# usb_host_slave.net
KiCad netlist of a schematic drawn in Altium Designer
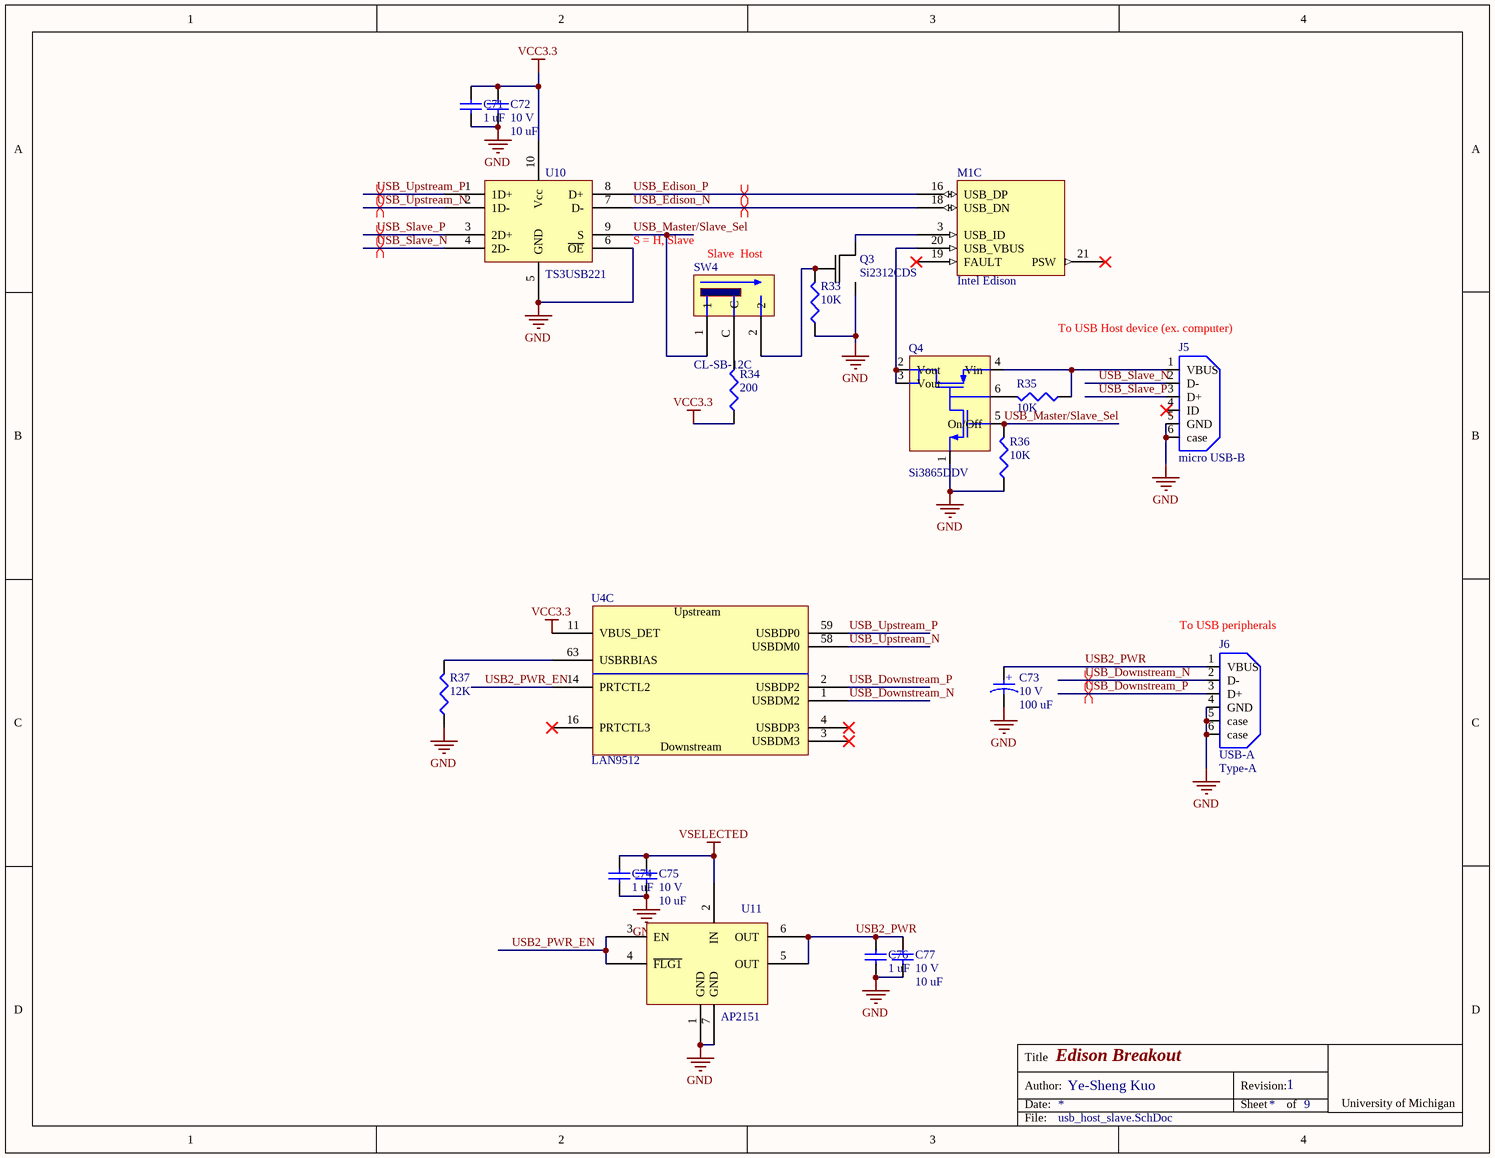
[diagram p0: usb_host_slave.SchDoc]

(export (version "E")
  (design (tool "Eeschema 10.0.6"))
  (components
    (comp (ref "C71")
      (value "1 uF")
      (footprint "0402")
      (description "Ceramic capacitor, 1 uF, 16V, 0402 package")
      (fields (field (name "TOLERANCE") "10%") (field (name "Comment") "Ceramic capacitor"))
      (libsource (lib "rlc") (part "C_1u_16V_0402_ceramic"))
    )
    (comp (ref "C72")
      (value "10 uF")
      (footprint "0603")
      (description "Ceramic capacitor, 10 uF, 10 V, 0603 package")
      (fields
        (field (name "TOLERANCE") "20%")
        (field (name "VOLTAGE RATED") "10 V")
        (field (name "Comment") "Ceramic capacitor")
      )
      (libsource (lib "rlc") (part "C_10u_10V_0603_ceramic"))
    )
    (comp (ref "C73")
      (value "100 uF")
      (footprint "1206 - POLAR MARKING")
      (description "Tantalum capacitor, 100 uF, 10 V, 1206 package")
      (fields
        (field (name "TOLERANCE") "20%")
        (field (name "VOLTAGE RATED") "10 V")
        (field (name "Comment") "Tantalum capacitor")
      )
      (libsource (lib "rlc") (part "C_100u_10V_1206_tantalum"))
    )
    (comp (ref "C74")
      (value "1 uF")
      (footprint "0402")
      (description "Ceramic capacitor, 1 uF, 16V, 0402 package")
      (fields (field (name "TOLERANCE") "10%") (field (name "Comment") "Ceramic capacitor"))
      (libsource (lib "rlc") (part "C_1u_16V_0402_ceramic"))
    )
    (comp (ref "C75")
      (value "10 uF")
      (footprint "0603")
      (description "Ceramic capacitor, 10 uF, 10 V, 0603 package")
      (fields
        (field (name "TOLERANCE") "20%")
        (field (name "VOLTAGE RATED") "10 V")
        (field (name "Comment") "Ceramic capacitor")
      )
      (libsource (lib "rlc") (part "C_10u_10V_0603_ceramic"))
    )
    (comp (ref "C76")
      (value "1 uF")
      (footprint "0402")
      (description "Ceramic capacitor, 1 uF, 16V, 0402 package")
      (fields (field (name "TOLERANCE") "10%") (field (name "Comment") "Ceramic capacitor"))
      (libsource (lib "rlc") (part "C_1u_16V_0402_ceramic"))
    )
    (comp (ref "C77")
      (value "10 uF")
      (footprint "0603")
      (description "Ceramic capacitor, 10 uF, 10 V, 0603 package")
      (fields
        (field (name "TOLERANCE") "20%")
        (field (name "VOLTAGE RATED") "10 V")
        (field (name "Comment") "Ceramic capacitor")
      )
      (libsource (lib "rlc") (part "C_10u_10V_0603_ceramic"))
    )
    (comp (ref "J5")
      (value "micro USB-B")
      (footprint "Micro USB-B")
      (description "CONN USB MICRO B RECPT SMT R/A")
      (libsource (lib "connectors") (part "Micro USB"))
    )
    (comp (ref "J6")
      (value "USB-A")
      (footprint "292303-2")
      (description "USB 2.0 Type A")
      (fields (field (name "TYPE") "Type-A"))
      (libsource (lib "connectors") (part "A105221-ND"))
    )
    (comp (ref "M1")
      (value "Intel Edison")
      (footprint "Intel Edison mating")
      (libsource (lib "edison") (part "Intel Edison"))
    )
    (comp (ref "Q3")
      (value "Si2312CDS")
      (footprint "SOT23-3")
      (description "N-Channel 20 V (D-S) MOSFET")
      (libsource (lib "transistors") (part "Si2312CDS"))
    )
    (comp (ref "Q4")
      (value "Si3865DDV")
      (footprint "TSOT-23")
      (description "Load Switch")
      (libsource (lib "power_switch") (part "Si3865DDV"))
    )
    (comp (ref "R33")
      (value "10K")
      (footprint "0402")
      (description "Chip resistor, 10K, 0402 package")
      (fields (field (name "TOLERANCE") "1%") (field (name "POWER") "1/16 W"))
      (libsource (lib "rlc") (part "R_10K_0402"))
    )
    (comp (ref "R34")
      (value "200")
      (footprint "0402")
      (description "Chip resistor, 200, 0402 package")
      (fields (field (name "TOLERANCE") "1%") (field (name "POWER") "1/16 W"))
      (libsource (lib "rlc") (part "R_200_0402"))
    )
    (comp (ref "R35")
      (value "10K")
      (footprint "0402")
      (description "Chip resistor, 10K, 0402 package")
      (fields (field (name "TOLERANCE") "1%") (field (name "POWER") "1/16 W"))
      (libsource (lib "rlc") (part "R_10K_0402"))
    )
    (comp (ref "R36")
      (value "10K")
      (footprint "0402")
      (description "Chip resistor, 10K, 0402 package")
      (fields (field (name "TOLERANCE") "1%") (field (name "POWER") "1/16 W"))
      (libsource (lib "rlc") (part "R_10K_0402"))
    )
    (comp (ref "R37")
      (value "12K")
      (footprint "0402")
      (description "Chip resistor, 12K, 0402 package")
      (fields (field (name "TOLERANCE") "1%") (field (name "POWER") "1/16 W"))
      (libsource (lib "rlc") (part "R_12K_0402"))
    )
    (comp (ref "SW4")
      (value "CL-SB-12C")
      (footprint "CL-SB-12C")
      (description "SPST Slide switch")
      (libsource (lib "switches") (part "CL-SB-12C"))
    )
    (comp (ref "U4")
      (value "LAN9512")
      (footprint "QFN-64")
      (description "USB 2.0 Hub and 10/100  Ethernet Controller")
      (libsource (lib "ethernet") (part "LAN9512"))
    )
    (comp (ref "U10")
      (value "TS3USB221")
      (footprint "PUQFN-10")
      (description "High-Speed USB 2.0 (480-Mbps) 1:2 Multiplexer – Demultiplexer  Switch With Single Enable")
      (libsource (lib "multiplexer") (part "TS3USB221"))
    )
    (comp (ref "U11")
      (value "AP2151")
      (footprint "U-DFN2018-6")
      (description "0.5A SINGLE CHANNEL CURRENT-LIMITED  POWER SWITCH WITH OUTPUT DISCHARGE")
      (libsource (lib "power_switch") (part "AP2151"))
    )
  )
  (nets
    (net (code "1") (name "/USB2_PWR") (class "Default")
      (node (ref "C73") (pin "1") (pintype "passive"))
      (node (ref "C76") (pin "1") (pintype "passive"))
      (node (ref "C77") (pin "1") (pintype "passive"))
      (node (ref "J6") (pin "1") (pinfunction "VBUS_1") (pintype "power_in"))
      (node (ref "U11") (pin "5") (pinfunction "OUT_5") (pintype "passive"))
      (node (ref "U11") (pin "6") (pinfunction "OUT_6") (pintype "passive"))
    )
    (net (code "2") (name "/USB2_PWR_EN") (class "Default")
      (node (ref "U11") (pin "3") (pinfunction "EN_3") (pintype "passive"))
      (node (ref "U11") (pin "4") (pinfunction "~{FLG1}_4") (pintype "passive"))
      (node (ref "U4") (pin "14") (pinfunction "PRTCTL2_14") (pintype "passive"))
    )
    (net (code "3") (name "/USB_Downstream_N") (class "Default")
      (node (ref "J6") (pin "2") (pinfunction "D-_2") (pintype "power_in"))
      (node (ref "U4") (pin "1") (pinfunction "USBDM2_1") (pintype "passive"))
    )
    (net (code "4") (name "/USB_Downstream_P") (class "Default")
      (node (ref "J6") (pin "3") (pinfunction "D+_3") (pintype "power_in"))
      (node (ref "U4") (pin "2") (pinfunction "USBDP2_2") (pintype "passive"))
    )
    (net (code "5") (name "/USB_Edison_N") (class "Default")
      (node (ref "M1") (pin "18") (pinfunction "USB_DN_18") (pintype "bidirectional"))
      (node (ref "U10") (pin "7") (pinfunction "D-_7") (pintype "passive"))
    )
    (net (code "6") (name "/USB_Edison_P") (class "Default")
      (node (ref "M1") (pin "16") (pinfunction "USB_DP_16") (pintype "bidirectional"))
      (node (ref "U10") (pin "8") (pinfunction "D+_8") (pintype "passive"))
    )
    (net (code "7") (name "/USB_Master{slash}Slave_Sel") (class "Default")
      (node (ref "Q4") (pin "5") (pinfunction "On/Off_5") (pintype "passive"))
      (node (ref "R36") (pin "1") (pintype "passive"))
      (node (ref "SW4") (pin "1") (pinfunction "1_1") (pintype "passive"))
      (node (ref "U10") (pin "9") (pinfunction "S_9") (pintype "passive"))
    )
    (net (code "8") (name "/USB_Slave_N") (class "Default")
      (node (ref "J5") (pin "2") (pinfunction "D-_2") (pintype "power_in"))
      (node (ref "U10") (pin "4") (pinfunction "2D-_4") (pintype "passive"))
    )
    (net (code "9") (name "/USB_Slave_P") (class "Default")
      (node (ref "J5") (pin "3") (pinfunction "D+_3") (pintype "power_in"))
      (node (ref "U10") (pin "3") (pinfunction "2D+_3") (pintype "passive"))
    )
    (net (code "10") (name "/USB_Upstream_N") (class "Default")
      (node (ref "U10") (pin "2") (pinfunction "1D-_2") (pintype "passive"))
      (node (ref "U4") (pin "58") (pinfunction "USBDM0_58") (pintype "passive"))
    )
    (net (code "11") (name "/USB_Upstream_P") (class "Default")
      (node (ref "U10") (pin "1") (pinfunction "1D+_1") (pintype "passive"))
      (node (ref "U4") (pin "59") (pinfunction "USBDP0_59") (pintype "passive"))
    )
    (net (code "12") (name "GND") (class "Default")
      (node (ref "C71") (pin "2") (pintype "passive"))
      (node (ref "C72") (pin "2") (pintype "passive"))
      (node (ref "C73") (pin "2") (pintype "passive"))
      (node (ref "C74") (pin "2") (pintype "passive"))
      (node (ref "C75") (pin "2") (pintype "passive"))
      (node (ref "C76") (pin "2") (pintype "passive"))
      (node (ref "C77") (pin "2") (pintype "passive"))
      (node (ref "J5") (pin "5") (pinfunction "GND_5") (pintype "power_in"))
      (node (ref "J5") (pin "6") (pinfunction "case_6") (pintype "power_in"))
      (node (ref "J6") (pin "4") (pinfunction "GND_4") (pintype "power_in"))
      (node (ref "J6") (pin "5") (pinfunction "case_5") (pintype "power_in"))
      (node (ref "J6") (pin "6") (pinfunction "case_6") (pintype "power_in"))
      (node (ref "Q3") (pin "2") (pinfunction "S_2") (pintype "passive"))
      (node (ref "Q4") (pin "1") (pintype "passive"))
      (node (ref "R33") (pin "2") (pintype "passive"))
      (node (ref "R36") (pin "2") (pintype "passive"))
      (node (ref "R37") (pin "2") (pintype "passive"))
      (node (ref "U10") (pin "5") (pinfunction "GND_5") (pintype "passive"))
      (node (ref "U10") (pin "6") (pinfunction "~{OE}_6") (pintype "passive"))
      (node (ref "U11") (pin "1") (pinfunction "GND_1") (pintype "passive"))
      (node (ref "U11") (pin "7") (pinfunction "GND_7") (pintype "passive"))
    )
    (net (code "13") (name "Net-(J5-VBUS)") (class "Default")
      (node (ref "J5") (pin "1") (pinfunction "VBUS_1") (pintype "power_in"))
      (node (ref "Q4") (pin "4") (pinfunction "Vin_4") (pintype "passive"))
      (node (ref "R35") (pin "2") (pintype "passive"))
    )
    (net (code "14") (name "Net-(M1C-USB_ID)") (class "Default")
      (node (ref "M1") (pin "3") (pinfunction "USB_ID_3") (pintype "input"))
      (node (ref "Q3") (pin "3") (pinfunction "D_3") (pintype "passive"))
    )
    (net (code "15") (name "Net-(M1C-USB_VBUS)") (class "Default")
      (node (ref "M1") (pin "20") (pinfunction "USB_VBUS_20") (pintype "input"))
      (node (ref "Q4") (pin "2") (pinfunction "Vout_2") (pintype "passive"))
      (node (ref "Q4") (pin "3") (pinfunction "Vout_3") (pintype "passive"))
    )
    (net (code "16") (name "Net-(Q3-G)") (class "Default")
      (node (ref "Q3") (pin "1") (pinfunction "G_1") (pintype "passive"))
      (node (ref "R33") (pin "1") (pintype "passive"))
      (node (ref "SW4") (pin "2") (pinfunction "2_2") (pintype "passive"))
    )
    (net (code "17") (name "Net-(Q4-Pad6)") (class "Default")
      (node (ref "Q4") (pin "6") (pintype "passive"))
      (node (ref "R35") (pin "1") (pintype "passive"))
    )
    (net (code "18") (name "Net-(R34-Pad1)") (class "Default")
      (node (ref "R34") (pin "1") (pintype "passive"))
      (node (ref "SW4") (pin "C") (pinfunction "C_C") (pintype "passive"))
    )
    (net (code "19") (name "Net-(U4C-USBRBIAS)") (class "Default")
      (node (ref "R37") (pin "1") (pintype "passive"))
      (node (ref "U4") (pin "63") (pinfunction "USBRBIAS_63") (pintype "passive"))
    )
    (net (code "20") (name "VCC3.3") (class "Default")
      (node (ref "C71") (pin "1") (pintype "passive"))
      (node (ref "C72") (pin "1") (pintype "passive"))
      (node (ref "R34") (pin "2") (pintype "passive"))
      (node (ref "U10") (pin "10") (pinfunction "Vcc_10") (pintype "passive"))
      (node (ref "U4") (pin "11") (pinfunction "VBUS_DET_11") (pintype "passive"))
    )
    (net (code "21") (name "VSELECTED") (class "Default")
      (node (ref "C74") (pin "1") (pintype "passive"))
      (node (ref "C75") (pin "1") (pintype "passive"))
      (node (ref "U11") (pin "2") (pinfunction "IN_2") (pintype "passive"))
    )
    (net (code "22") (name "unconnected-(J5-ID-Pad4)") (class "Default")
      (node (ref "J5") (pin "4") (pinfunction "ID_4") (pintype "power_in+no_connect"))
    )
    (net (code "23") (name "unconnected-(M1C-FAULT-Pad19)") (class "Default")
      (node (ref "M1") (pin "19") (pinfunction "FAULT_19") (pintype "input+no_connect"))
    )
    (net (code "24") (name "unconnected-(M1C-PSW-Pad21)") (class "Default")
      (node (ref "M1") (pin "21") (pinfunction "PSW_21") (pintype "output+no_connect"))
    )
    (net (code "25") (name "unconnected-(U4C-PRTCTL3-Pad16)") (class "Default")
      (node (ref "U4") (pin "16") (pinfunction "PRTCTL3_16") (pintype "passive+no_connect"))
    )
    (net (code "26") (name "unconnected-(U4C-USBDM3-Pad3)") (class "Default")
      (node (ref "U4") (pin "3") (pinfunction "USBDM3_3") (pintype "passive+no_connect"))
    )
    (net (code "27") (name "unconnected-(U4C-USBDP3-Pad4)") (class "Default")
      (node (ref "U4") (pin "4") (pinfunction "USBDP3_4") (pintype "passive+no_connect"))
    )
  )
)
